# PLD_Gyroscopes.net
KiCad netlist of a schematic drawn in Altium Designer
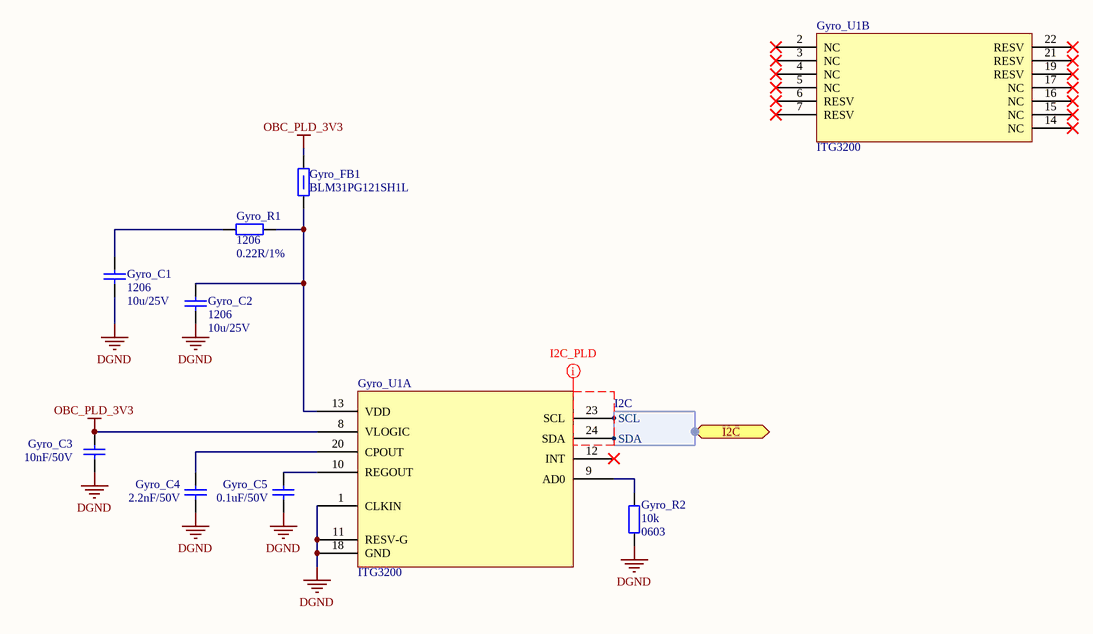
[diagram p0: PLD_Gyroscopes.SchDoc]

(export (version "E")
  (design (tool "Eeschema 10.0.6"))
  (components
    (comp (ref "Gyro_C1")
      (value "10u/25V")
      (footprint "SMD_Capacitor_1206")
      (description "Ceramic Cap Kemet COTS 1u/25V X7R 1206")
      (fields
        (field (name "MANUFACTURERPARTNUMBER") "C1206T105K3RALTU")
        (field (name "MANUFACTURER") "Kemet")
        (field (name "PACKAGE") "1206")
      )
      (libsource (lib "capacitors") (part "Cer_C1206T105K3RALTU"))
    )
    (comp (ref "Gyro_C2")
      (value "10u/25V")
      (footprint "SMD_Capacitor_1206")
      (description "Ceramic Cap Kemet COTS 1u/25V X7R 1206")
      (fields
        (field (name "MANUFACTURERPARTNUMBER") "C1206T105K3RALTU")
        (field (name "MANUFACTURER") "Kemet")
        (field (name "PACKAGE") "1206")
      )
      (libsource (lib "capacitors") (part "Cer_C1206T105K3RALTU"))
    )
    (comp (ref "Gyro_C3")
      (value "10nF/50V")
      (footprint "SMD_Capacitor_0603")
      (description "Ceramic Cap Kemet COTS 100n/50V X7R 0603")
      (fields
        (field (name "MANUFACTURER") "Kemet")
        (field (name "MANUFACTURERPARTNUMBER") "C0603T104K5RALTU")
      )
      (libsource (lib "capacitors") (part "Cer_C0603T104K5RALTU"))
    )
    (comp (ref "Gyro_C4")
      (value "2.2nF/50V")
      (footprint "SMD_Capacitor_0603")
      (description "Ceramic Cap Kemet COTS 100n/50V X7R 0603")
      (fields
        (field (name "MANUFACTURER") "Kemet")
        (field (name "MANUFACTURERPARTNUMBER") "C0603T104K5RALTU")
      )
      (libsource (lib "capacitors") (part "Cer_C0603T104K5RALTU"))
    )
    (comp (ref "Gyro_C5")
      (value "0.1uF/50V")
      (footprint "SMD_Capacitor_0603")
      (description "Ceramic Cap Kemet COTS 100n/50V X7R 0603")
      (fields
        (field (name "MANUFACTURER") "Kemet")
        (field (name "MANUFACTURERPARTNUMBER") "C0603T104K5RALTU")
      )
      (libsource (lib "capacitors") (part "Cer_C0603T104K5RALTU"))
    )
    (comp (ref "Gyro_FB1")
      (value "120R/100MHz")
      (footprint "SMD_FerriteBead_1206")
      (description "Ferrite bead, 1206, 0.02HM, 3.5A.")
      (fields (field (name "MANUFACTURER") "Murata") (field (name "MANUFACTURERPARTNUMBER") "BLM31PG121SH1L"))
      (libsource (lib "inductors") (part "BLM31PG121SH1L"))
    )
    (comp (ref "Gyro_R1")
      (value "0.22R/1%")
      (footprint "SMD_Resistor_1206")
      (description "Panasonic Resistor 0.22R 1% 1206 330mW")
      (fields
        (field (name "MANUFACTURER") "Panasonic")
        (field (name "MANUFACTURERPARTNUMBER") "ERJ-8BQFR22V")
        (field (name "PACKAGE") "1206")
      )
      (libsource (lib "resistors") (part "ERJ-8BQFR22V"))
    )
    (comp (ref "Gyro_R2")
      (value "10k")
      (footprint "SMD_Resistor_0603")
      (fields (field (name "PACKAGE") "0603"))
      (libsource (lib "resistors") (part "Res"))
    )
    (comp (ref "Gyro_U1") (value "ITG3200") (footprint "QFN24_4x4") (libsource (lib "mems") (part "ITG3200")))
  )
  (nets
    (net (code "2") (name "/SCL") (class "Default")
      (node (ref "Gyro_U1") (pin "23") (pinfunction "SCL_23") (pintype "passive"))
    )
    (net (code "3") (name "/SDA") (class "Default")
      (node (ref "Gyro_U1") (pin "24") (pinfunction "SDA_24") (pintype "passive"))
    )
    (net (code "5") (name "DGND") (class "Default")
      (node (ref "Gyro_C1") (pin "2") (pinfunction "2_2") (pintype "passive"))
      (node (ref "Gyro_C2") (pin "2") (pinfunction "2_2") (pintype "passive"))
      (node (ref "Gyro_C3") (pin "2") (pinfunction "2_2") (pintype "passive"))
      (node (ref "Gyro_C4") (pin "2") (pinfunction "2_2") (pintype "passive"))
      (node (ref "Gyro_C5") (pin "2") (pinfunction "2_2") (pintype "passive"))
      (node (ref "Gyro_R2") (pin "2") (pinfunction "2_2") (pintype "passive"))
      (node (ref "Gyro_U1") (pin "1") (pinfunction "CLKIN_1") (pintype "passive"))
      (node (ref "Gyro_U1") (pin "11") (pinfunction "RESV-G_11") (pintype "passive"))
      (node (ref "Gyro_U1") (pin "18") (pinfunction "GND_18") (pintype "passive"))
    )
    (net (code "6") (name "Net-(Gyro_C1-Pad1)") (class "Default")
      (node (ref "Gyro_C1") (pin "1") (pinfunction "1_1") (pintype "passive"))
      (node (ref "Gyro_R1") (pin "1") (pinfunction "1_1") (pintype "passive"))
    )
    (net (code "7") (name "Net-(Gyro_U1A-AD0)") (class "Default")
      (node (ref "Gyro_R2") (pin "1") (pinfunction "1_1") (pintype "passive"))
      (node (ref "Gyro_U1") (pin "9") (pinfunction "AD0_9") (pintype "passive"))
    )
    (net (code "8") (name "Net-(Gyro_U1A-CPOUT)") (class "Default")
      (node (ref "Gyro_C4") (pin "1") (pinfunction "1_1") (pintype "passive"))
      (node (ref "Gyro_U1") (pin "20") (pinfunction "CPOUT_20") (pintype "passive"))
    )
    (net (code "9") (name "Net-(Gyro_U1A-REGOUT)") (class "Default")
      (node (ref "Gyro_C5") (pin "1") (pinfunction "1_1") (pintype "passive"))
      (node (ref "Gyro_U1") (pin "10") (pinfunction "REGOUT_10") (pintype "passive"))
    )
    (net (code "10") (name "Net-(Gyro_U1A-VDD)") (class "Default")
      (node (ref "Gyro_C2") (pin "1") (pinfunction "1_1") (pintype "passive"))
      (node (ref "Gyro_FB1") (pin "2") (pinfunction "2_2") (pintype "passive"))
      (node (ref "Gyro_R1") (pin "2") (pinfunction "2_2") (pintype "passive"))
      (node (ref "Gyro_U1") (pin "13") (pinfunction "VDD_13") (pintype "passive"))
    )
    (net (code "11") (name "OBC_PLD_3V3") (class "Default")
      (node (ref "Gyro_C3") (pin "1") (pinfunction "1_1") (pintype "passive"))
      (node (ref "Gyro_FB1") (pin "1") (pinfunction "1_1") (pintype "passive"))
      (node (ref "Gyro_U1") (pin "8") (pinfunction "VLOGIC_8") (pintype "passive"))
    )
    (net (code "12") (name "unconnected-(Gyro_U1A-INT-Pad12)") (class "Default")
      (node (ref "Gyro_U1") (pin "12") (pinfunction "INT_12") (pintype "passive+no_connect"))
    )
    (net (code "13") (name "unconnected-(Gyro_U1B-NC-Pad2)") (class "Default")
      (node (ref "Gyro_U1") (pin "2") (pinfunction "NC_2") (pintype "passive+no_connect"))
    )
    (net (code "14") (name "unconnected-(Gyro_U1B-NC-Pad3)") (class "Default")
      (node (ref "Gyro_U1") (pin "3") (pinfunction "NC_3") (pintype "passive+no_connect"))
    )
    (net (code "15") (name "unconnected-(Gyro_U1B-NC-Pad4)") (class "Default")
      (node (ref "Gyro_U1") (pin "4") (pinfunction "NC_4") (pintype "passive+no_connect"))
    )
    (net (code "16") (name "unconnected-(Gyro_U1B-NC-Pad5)") (class "Default")
      (node (ref "Gyro_U1") (pin "5") (pinfunction "NC_5") (pintype "passive+no_connect"))
    )
    (net (code "17") (name "unconnected-(Gyro_U1B-NC-Pad14)") (class "Default")
      (node (ref "Gyro_U1") (pin "14") (pinfunction "NC_14") (pintype "passive+no_connect"))
    )
    (net (code "18") (name "unconnected-(Gyro_U1B-NC-Pad15)") (class "Default")
      (node (ref "Gyro_U1") (pin "15") (pinfunction "NC_15") (pintype "passive+no_connect"))
    )
    (net (code "19") (name "unconnected-(Gyro_U1B-NC-Pad16)") (class "Default")
      (node (ref "Gyro_U1") (pin "16") (pinfunction "NC_16") (pintype "passive+no_connect"))
    )
    (net (code "20") (name "unconnected-(Gyro_U1B-NC-Pad17)") (class "Default")
      (node (ref "Gyro_U1") (pin "17") (pinfunction "NC_17") (pintype "passive+no_connect"))
    )
    (net (code "21") (name "unconnected-(Gyro_U1B-RESV-Pad6)") (class "Default")
      (node (ref "Gyro_U1") (pin "6") (pinfunction "RESV_6") (pintype "passive+no_connect"))
    )
    (net (code "22") (name "unconnected-(Gyro_U1B-RESV-Pad7)") (class "Default")
      (node (ref "Gyro_U1") (pin "7") (pinfunction "RESV_7") (pintype "passive+no_connect"))
    )
    (net (code "23") (name "unconnected-(Gyro_U1B-RESV-Pad19)") (class "Default")
      (node (ref "Gyro_U1") (pin "19") (pinfunction "RESV_19") (pintype "passive+no_connect"))
    )
    (net (code "24") (name "unconnected-(Gyro_U1B-RESV-Pad21)") (class "Default")
      (node (ref "Gyro_U1") (pin "21") (pinfunction "RESV_21") (pintype "passive+no_connect"))
    )
    (net (code "25") (name "unconnected-(Gyro_U1B-RESV-Pad22)") (class "Default")
      (node (ref "Gyro_U1") (pin "22") (pinfunction "RESV_22") (pintype "passive+no_connect"))
    )
  )
)
